# hbridge.net
KiCad netlist of a schematic drawn in EAGLE
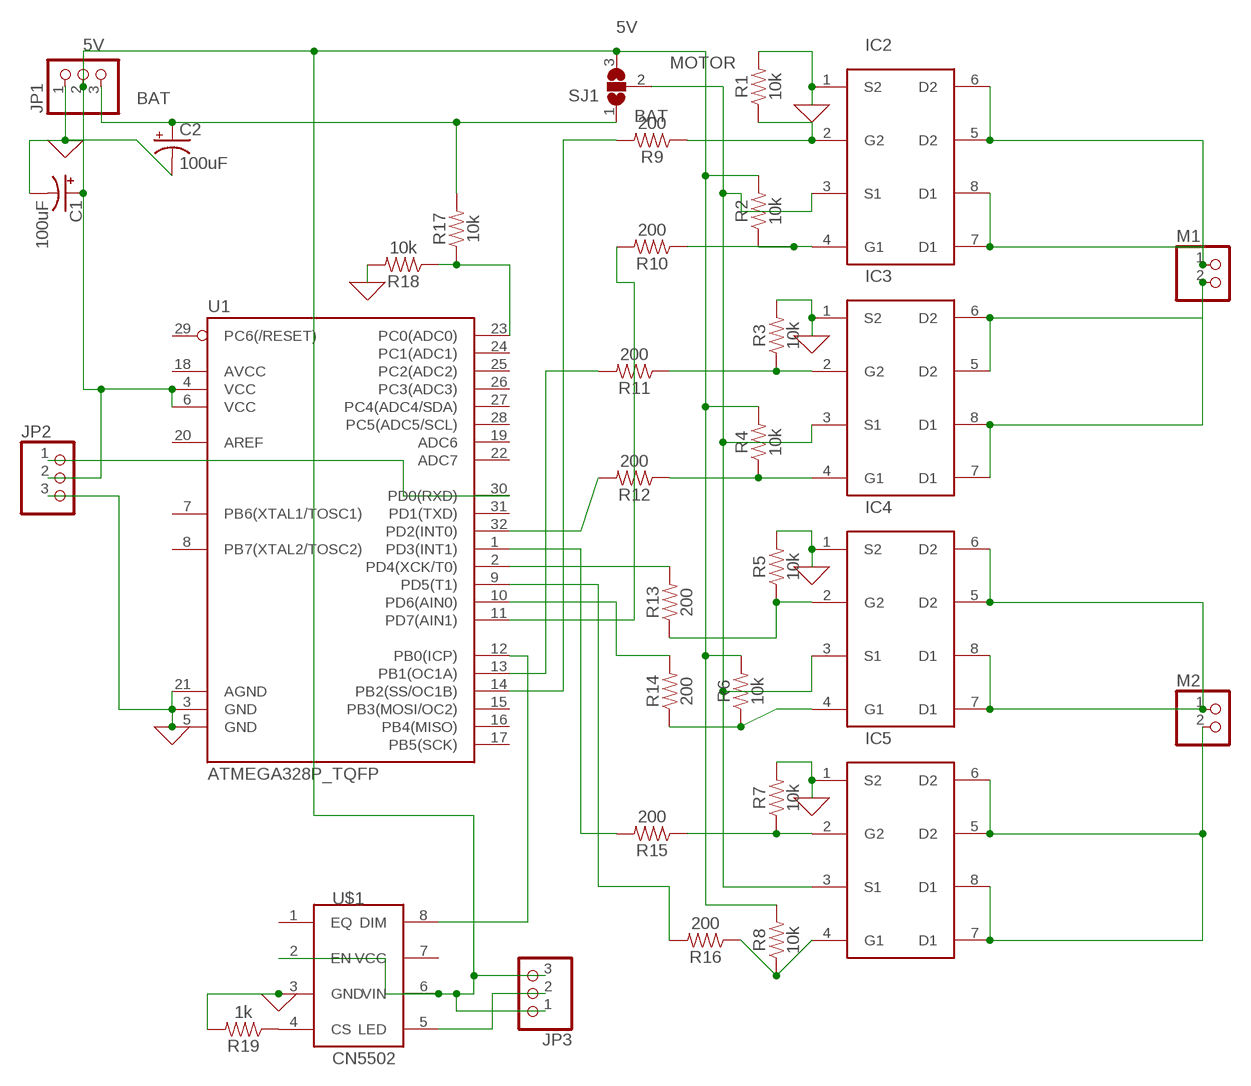
[diagram p0: schematic, sheet 1]

(export (version "E")
  (design (tool "Eeschema 10.0.6"))
  (components
    (comp (ref "C1")
      (value "100uF")
      (footprint "eagle-import:CPOL-RADIAL-2.5MM-6.5MM")
      (libsource (lib "eagle-import") (part "100UF-POLAR-RADIAL-2.5MM-25V-20%"))
    )
    (comp (ref "C2")
      (value "100uF")
      (footprint "eagle-import:CPOL-RADIAL-2.5MM-6.5MM")
      (libsource (lib "eagle-import") (part "100UF-POLAR-RADIAL-2.5MM-25V-20%"))
    )
    (comp (ref "IC2")
      (value "AO4606SOIC8")
      (footprint "eagle-import:SOIC8")
      (libsource (lib "eagle-import") (part "AO4606SOIC8"))
    )
    (comp (ref "IC3")
      (value "AO4606SOIC8")
      (footprint "eagle-import:SOIC8")
      (libsource (lib "eagle-import") (part "AO4606SOIC8"))
    )
    (comp (ref "IC4")
      (value "AO4606SOIC8")
      (footprint "eagle-import:SOIC8")
      (libsource (lib "eagle-import") (part "AO4606SOIC8"))
    )
    (comp (ref "IC5")
      (value "AO4606SOIC8")
      (footprint "eagle-import:SOIC8")
      (libsource (lib "eagle-import") (part "AO4606SOIC8"))
    )
    (comp (ref "JP1")
      (value "PINHD-1X3")
      (footprint "eagle-import:1X03")
      (libsource (lib "eagle-import") (part "PINHD-1X3"))
    )
    (comp (ref "JP2")
      (value "PINHD-1X3")
      (footprint "eagle-import:1X03")
      (libsource (lib "eagle-import") (part "PINHD-1X3"))
    )
    (comp (ref "JP3")
      (value "PINHD-1X3")
      (footprint "eagle-import:1X03")
      (libsource (lib "eagle-import") (part "PINHD-1X3"))
    )
    (comp (ref "M1")
      (value "PINHD-1X2")
      (footprint "eagle-import:1X02")
      (libsource (lib "eagle-import") (part "PINHD-1X2"))
    )
    (comp (ref "M2")
      (value "PINHD-1X2")
      (footprint "eagle-import:1X02")
      (libsource (lib "eagle-import") (part "PINHD-1X2"))
    )
    (comp (ref "R1")
      (value "10k")
      (footprint "eagle-import:0603")
      (libsource (lib "eagle-import") (part "10KOHM-0603-1/10W-1%"))
    )
    (comp (ref "R2")
      (value "10k")
      (footprint "eagle-import:0603")
      (libsource (lib "eagle-import") (part "10KOHM-0603-1/10W-1%"))
    )
    (comp (ref "R3")
      (value "10k")
      (footprint "eagle-import:0603")
      (libsource (lib "eagle-import") (part "10KOHM-0603-1/10W-1%"))
    )
    (comp (ref "R4")
      (value "10k")
      (footprint "eagle-import:0603")
      (libsource (lib "eagle-import") (part "10KOHM-0603-1/10W-1%"))
    )
    (comp (ref "R5")
      (value "10k")
      (footprint "eagle-import:0603")
      (libsource (lib "eagle-import") (part "10KOHM-0603-1/10W-1%"))
    )
    (comp (ref "R6")
      (value "10k")
      (footprint "eagle-import:0603")
      (libsource (lib "eagle-import") (part "10KOHM-0603-1/10W-1%"))
    )
    (comp (ref "R7")
      (value "10k")
      (footprint "eagle-import:0603")
      (libsource (lib "eagle-import") (part "10KOHM-0603-1/10W-1%"))
    )
    (comp (ref "R8")
      (value "10k")
      (footprint "eagle-import:0603")
      (libsource (lib "eagle-import") (part "10KOHM-0603-1/10W-1%"))
    )
    (comp (ref "R9")
      (value "200")
      (footprint "eagle-import:0603")
      (libsource (lib "eagle-import") (part "200OHM-0603-1/10W-1%"))
    )
    (comp (ref "R10")
      (value "200")
      (footprint "eagle-import:0603")
      (libsource (lib "eagle-import") (part "200OHM-0603-1/10W-1%"))
    )
    (comp (ref "R11")
      (value "200")
      (footprint "eagle-import:0603")
      (libsource (lib "eagle-import") (part "200OHM-0603-1/10W-1%"))
    )
    (comp (ref "R12")
      (value "200")
      (footprint "eagle-import:0603")
      (libsource (lib "eagle-import") (part "200OHM-0603-1/10W-1%"))
    )
    (comp (ref "R13")
      (value "200")
      (footprint "eagle-import:0603")
      (libsource (lib "eagle-import") (part "200OHM-0603-1/10W-1%"))
    )
    (comp (ref "R14")
      (value "200")
      (footprint "eagle-import:0603")
      (libsource (lib "eagle-import") (part "200OHM-0603-1/10W-1%"))
    )
    (comp (ref "R15")
      (value "200")
      (footprint "eagle-import:0603")
      (libsource (lib "eagle-import") (part "200OHM-0603-1/10W-1%"))
    )
    (comp (ref "R16")
      (value "200")
      (footprint "eagle-import:0603")
      (libsource (lib "eagle-import") (part "200OHM-0603-1/10W-1%"))
    )
    (comp (ref "R17")
      (value "10k")
      (footprint "eagle-import:AXIAL-0.3")
      (libsource (lib "eagle-import") (part "10KOHM-HORIZ-1/4W-1%"))
    )
    (comp (ref "R18")
      (value "10k")
      (footprint "eagle-import:AXIAL-0.3")
      (libsource (lib "eagle-import") (part "10KOHM-HORIZ-1/4W-1%"))
    )
    (comp (ref "R19")
      (value "1k")
      (footprint "eagle-import:AXIAL-0.3")
      (libsource (lib "eagle-import") (part "1KOHM-HORIZ-1/4W-1%"))
    )
    (comp (ref "SJ1")
      (value "SJ2W")
      (footprint "eagle-import:SJ_2")
      (libsource (lib "eagle-import") (part "SJ2W"))
    )
    (comp (ref "U$1")
      (value "CN5502")
      (footprint "eagle-import:SOIC8")
      (libsource (lib "eagle-import") (part "CN5502"))
    )
    (comp (ref "U1")
      (value "ATMEGA328P_TQFP")
      (footprint "eagle-import:TQFP32-08")
      (libsource (lib "eagle-import") (part "ATMEGA328P_TQFP"))
    )
  )
  (nets
    (net (code "1") (name "/5V") (class "Default")
      (node (ref "C1") (pin "1") (pinfunction "+_1") (pintype "passive"))
      (node (ref "JP1") (pin "2") (pinfunction "2_2") (pintype "passive"))
      (node (ref "JP2") (pin "2") (pinfunction "2_2") (pintype "passive"))
      (node (ref "JP3") (pin "1") (pinfunction "1_1") (pintype "passive"))
      (node (ref "JP3") (pin "3") (pinfunction "3_3") (pintype "passive"))
      (node (ref "R2") (pin "2") (pinfunction "2_2") (pintype "passive"))
      (node (ref "R4") (pin "2") (pinfunction "2_2") (pintype "passive"))
      (node (ref "R6") (pin "2") (pinfunction "2_2") (pintype "passive"))
      (node (ref "R8") (pin "2") (pinfunction "2_2") (pintype "passive"))
      (node (ref "SJ1") (pin "3") (pinfunction "3_3") (pintype "passive"))
      (node (ref "U$1") (pin "2") (pinfunction "EN_2") (pintype "input"))
      (node (ref "U$1") (pin "6") (pinfunction "VIN_6") (pintype "power_in"))
      (node (ref "U1") (pin "4") (pinfunction "VCC_4") (pintype "bidirectional"))
      (node (ref "U1") (pin "6") (pinfunction "VCC_6") (pintype "bidirectional"))
    )
    (net (code "2") (name "/BAT") (class "Default")
      (node (ref "C2") (pin "1") (pinfunction "+_1") (pintype "passive"))
      (node (ref "JP1") (pin "3") (pinfunction "3_3") (pintype "passive"))
      (node (ref "R17") (pin "P$2") (pinfunction "2_P$2") (pintype "passive"))
      (node (ref "SJ1") (pin "1") (pinfunction "1_1") (pintype "passive"))
    )
    (net (code "3") (name "/MOTOR") (class "Default")
      (node (ref "IC2") (pin "3") (pinfunction "S1_3") (pintype "bidirectional"))
      (node (ref "IC3") (pin "3") (pinfunction "S1_3") (pintype "bidirectional"))
      (node (ref "IC4") (pin "3") (pinfunction "S1_3") (pintype "bidirectional"))
      (node (ref "IC5") (pin "3") (pinfunction "S1_3") (pintype "bidirectional"))
      (node (ref "SJ1") (pin "2") (pinfunction "2_2") (pintype "passive"))
    )
    (net (code "4") (name "/VCC") (class "Default")
      (node (ref "U$1") (pin "7") (pinfunction "VCC_7") (pintype "power_in"))
    )
    (net (code "5") (name "GND") (class "Default")
      (node (ref "C1") (pin "2") (pinfunction "-_2") (pintype "passive"))
      (node (ref "C2") (pin "2") (pinfunction "-_2") (pintype "passive"))
      (node (ref "IC2") (pin "1") (pinfunction "S2_1") (pintype "bidirectional"))
      (node (ref "IC3") (pin "1") (pinfunction "S2_1") (pintype "bidirectional"))
      (node (ref "IC4") (pin "1") (pinfunction "S2_1") (pintype "bidirectional"))
      (node (ref "IC5") (pin "1") (pinfunction "S2_1") (pintype "bidirectional"))
      (node (ref "JP1") (pin "1") (pinfunction "1_1") (pintype "passive"))
      (node (ref "JP2") (pin "3") (pinfunction "3_3") (pintype "passive"))
      (node (ref "R1") (pin "2") (pinfunction "2_2") (pintype "passive"))
      (node (ref "R18") (pin "P$2") (pinfunction "2_P$2") (pintype "passive"))
      (node (ref "R19") (pin "P$2") (pinfunction "2_P$2") (pintype "passive"))
      (node (ref "R3") (pin "2") (pinfunction "2_2") (pintype "passive"))
      (node (ref "R5") (pin "2") (pinfunction "2_2") (pintype "passive"))
      (node (ref "R7") (pin "2") (pinfunction "2_2") (pintype "passive"))
      (node (ref "U$1") (pin "3") (pinfunction "GND_3") (pintype "power_in"))
      (node (ref "U1") (pin "21") (pinfunction "AGND_21") (pintype "bidirectional"))
      (node (ref "U1") (pin "3") (pinfunction "GND_3") (pintype "bidirectional"))
      (node (ref "U1") (pin "5") (pinfunction "GND_5") (pintype "bidirectional"))
    )
    (net (code "6") (name "Net-(IC2-D1-Pad7)") (class "Default")
      (node (ref "IC2") (pin "5") (pinfunction "D2_5") (pintype "bidirectional"))
      (node (ref "IC2") (pin "6") (pinfunction "D2_6") (pintype "bidirectional"))
      (node (ref "IC2") (pin "7") (pinfunction "D1_7") (pintype "bidirectional"))
      (node (ref "IC2") (pin "8") (pinfunction "D1_8") (pintype "bidirectional"))
      (node (ref "M1") (pin "1") (pinfunction "1_1") (pintype "passive"))
    )
    (net (code "7") (name "Net-(IC2-G1)") (class "Default")
      (node (ref "IC2") (pin "4") (pinfunction "G1_4") (pintype "bidirectional"))
      (node (ref "R10") (pin "1") (pinfunction "1_1") (pintype "passive"))
      (node (ref "R2") (pin "1") (pinfunction "1_1") (pintype "passive"))
    )
    (net (code "8") (name "Net-(IC2-G2)") (class "Default")
      (node (ref "IC2") (pin "2") (pinfunction "G2_2") (pintype "bidirectional"))
      (node (ref "R1") (pin "1") (pinfunction "1_1") (pintype "passive"))
      (node (ref "R9") (pin "1") (pinfunction "1_1") (pintype "passive"))
    )
    (net (code "9") (name "Net-(IC3-D1-Pad7)") (class "Default")
      (node (ref "IC3") (pin "5") (pinfunction "D2_5") (pintype "bidirectional"))
      (node (ref "IC3") (pin "6") (pinfunction "D2_6") (pintype "bidirectional"))
      (node (ref "IC3") (pin "7") (pinfunction "D1_7") (pintype "bidirectional"))
      (node (ref "IC3") (pin "8") (pinfunction "D1_8") (pintype "bidirectional"))
      (node (ref "M1") (pin "2") (pinfunction "2_2") (pintype "passive"))
    )
    (net (code "10") (name "Net-(IC3-G1)") (class "Default")
      (node (ref "IC3") (pin "4") (pinfunction "G1_4") (pintype "bidirectional"))
      (node (ref "R12") (pin "1") (pinfunction "1_1") (pintype "passive"))
      (node (ref "R4") (pin "1") (pinfunction "1_1") (pintype "passive"))
    )
    (net (code "11") (name "Net-(IC3-G2)") (class "Default")
      (node (ref "IC3") (pin "2") (pinfunction "G2_2") (pintype "bidirectional"))
      (node (ref "R11") (pin "1") (pinfunction "1_1") (pintype "passive"))
      (node (ref "R3") (pin "1") (pinfunction "1_1") (pintype "passive"))
    )
    (net (code "12") (name "Net-(IC4-D1-Pad7)") (class "Default")
      (node (ref "IC4") (pin "5") (pinfunction "D2_5") (pintype "bidirectional"))
      (node (ref "IC4") (pin "6") (pinfunction "D2_6") (pintype "bidirectional"))
      (node (ref "IC4") (pin "7") (pinfunction "D1_7") (pintype "bidirectional"))
      (node (ref "IC4") (pin "8") (pinfunction "D1_8") (pintype "bidirectional"))
      (node (ref "M2") (pin "1") (pinfunction "1_1") (pintype "passive"))
    )
    (net (code "13") (name "Net-(IC4-G1)") (class "Default")
      (node (ref "IC4") (pin "4") (pinfunction "G1_4") (pintype "bidirectional"))
      (node (ref "R14") (pin "1") (pinfunction "1_1") (pintype "passive"))
      (node (ref "R6") (pin "1") (pinfunction "1_1") (pintype "passive"))
    )
    (net (code "14") (name "Net-(IC4-G2)") (class "Default")
      (node (ref "IC4") (pin "2") (pinfunction "G2_2") (pintype "bidirectional"))
      (node (ref "R13") (pin "1") (pinfunction "1_1") (pintype "passive"))
      (node (ref "R5") (pin "1") (pinfunction "1_1") (pintype "passive"))
    )
    (net (code "15") (name "Net-(IC5-D1-Pad7)") (class "Default")
      (node (ref "IC5") (pin "5") (pinfunction "D2_5") (pintype "bidirectional"))
      (node (ref "IC5") (pin "6") (pinfunction "D2_6") (pintype "bidirectional"))
      (node (ref "IC5") (pin "7") (pinfunction "D1_7") (pintype "bidirectional"))
      (node (ref "IC5") (pin "8") (pinfunction "D1_8") (pintype "bidirectional"))
      (node (ref "M2") (pin "2") (pinfunction "2_2") (pintype "passive"))
    )
    (net (code "16") (name "Net-(IC5-G1)") (class "Default")
      (node (ref "IC5") (pin "4") (pinfunction "G1_4") (pintype "bidirectional"))
      (node (ref "R16") (pin "1") (pinfunction "1_1") (pintype "passive"))
      (node (ref "R8") (pin "1") (pinfunction "1_1") (pintype "passive"))
    )
    (net (code "17") (name "Net-(IC5-G2)") (class "Default")
      (node (ref "IC5") (pin "2") (pinfunction "G2_2") (pintype "bidirectional"))
      (node (ref "R15") (pin "1") (pinfunction "1_1") (pintype "passive"))
      (node (ref "R7") (pin "1") (pinfunction "1_1") (pintype "passive"))
    )
    (net (code "18") (name "Net-(R17-1)") (class "Default")
      (node (ref "R17") (pin "P$1") (pinfunction "1_P$1") (pintype "passive"))
      (node (ref "R18") (pin "P$1") (pinfunction "1_P$1") (pintype "passive"))
      (node (ref "U1") (pin "23") (pinfunction "PC0(ADC0)_23") (pintype "bidirectional"))
    )
    (net (code "19") (name "Net-(R19-1)") (class "Default")
      (node (ref "R19") (pin "P$1") (pinfunction "1_P$1") (pintype "passive"))
      (node (ref "U$1") (pin "4") (pinfunction "CS_4") (pintype "output"))
    )
    (net (code "20") (name "Net-(U$1-DIM)") (class "Default")
      (node (ref "U$1") (pin "8") (pinfunction "DIM_8") (pintype "input"))
      (node (ref "U1") (pin "12") (pinfunction "PB0(ICP)_12") (pintype "bidirectional"))
    )
    (net (code "21") (name "Net-(U$1-LED)") (class "Default")
      (node (ref "JP3") (pin "2") (pinfunction "2_2") (pintype "passive"))
      (node (ref "U$1") (pin "5") (pinfunction "LED_5") (pintype "output"))
    )
    (net (code "22") (name "Net-(U1-PB1(OC1A))") (class "Default")
      (node (ref "R11") (pin "2") (pinfunction "2_2") (pintype "passive"))
      (node (ref "U1") (pin "13") (pinfunction "PB1(OC1A)_13") (pintype "bidirectional"))
    )
    (net (code "23") (name "Net-(U1-PB2(SS{slash}OC1B))") (class "Default")
      (node (ref "R9") (pin "2") (pinfunction "2_2") (pintype "passive"))
      (node (ref "U1") (pin "14") (pinfunction "PB2(SS/OC1B)_14") (pintype "bidirectional"))
    )
    (net (code "24") (name "Net-(U1-PD0(RXD))") (class "Default")
      (node (ref "JP2") (pin "1") (pinfunction "1_1") (pintype "passive"))
      (node (ref "U1") (pin "30") (pinfunction "PD0(RXD)_30") (pintype "bidirectional"))
    )
    (net (code "25") (name "Net-(U1-PD2(INT0))") (class "Default")
      (node (ref "R12") (pin "2") (pinfunction "2_2") (pintype "passive"))
      (node (ref "U1") (pin "32") (pinfunction "PD2(INT0)_32") (pintype "bidirectional"))
    )
    (net (code "26") (name "Net-(U1-PD3(INT1))") (class "Default")
      (node (ref "R15") (pin "2") (pinfunction "2_2") (pintype "passive"))
      (node (ref "U1") (pin "1") (pinfunction "PD3(INT1)_1") (pintype "bidirectional"))
    )
    (net (code "27") (name "Net-(U1-PD4(XCK{slash}T0))") (class "Default")
      (node (ref "R13") (pin "2") (pinfunction "2_2") (pintype "passive"))
      (node (ref "U1") (pin "2") (pinfunction "PD4(XCK/T0)_2") (pintype "bidirectional"))
    )
    (net (code "28") (name "Net-(U1-PD5(T1))") (class "Default")
      (node (ref "R16") (pin "2") (pinfunction "2_2") (pintype "passive"))
      (node (ref "U1") (pin "9") (pinfunction "PD5(T1)_9") (pintype "bidirectional"))
    )
    (net (code "29") (name "Net-(U1-PD6(AIN0))") (class "Default")
      (node (ref "R14") (pin "2") (pinfunction "2_2") (pintype "passive"))
      (node (ref "U1") (pin "10") (pinfunction "PD6(AIN0)_10") (pintype "bidirectional"))
    )
    (net (code "30") (name "Net-(U1-PD7(AIN1))") (class "Default")
      (node (ref "R10") (pin "2") (pinfunction "2_2") (pintype "passive"))
      (node (ref "U1") (pin "11") (pinfunction "PD7(AIN1)_11") (pintype "bidirectional"))
    )
    (net (code "31") (name "unconnected-(U$1-EQ-Pad1)") (class "Default")
      (node (ref "U$1") (pin "1") (pinfunction "EQ_1") (pintype "output"))
    )
    (net (code "32") (name "unconnected-(U1-ADC6-Pad19)") (class "Default")
      (node (ref "U1") (pin "19") (pinfunction "ADC6_19") (pintype "bidirectional"))
    )
    (net (code "33") (name "unconnected-(U1-ADC7-Pad22)") (class "Default")
      (node (ref "U1") (pin "22") (pinfunction "ADC7_22") (pintype "bidirectional"))
    )
    (net (code "34") (name "unconnected-(U1-AREF-Pad20)") (class "Default")
      (node (ref "U1") (pin "20") (pinfunction "AREF_20") (pintype "bidirectional"))
    )
    (net (code "35") (name "unconnected-(U1-AVCC-Pad18)") (class "Default")
      (node (ref "U1") (pin "18") (pinfunction "AVCC_18") (pintype "bidirectional"))
    )
    (net (code "36") (name "unconnected-(U1-PB3(MOSI{slash}OC2)-Pad15)") (class "Default")
      (node (ref "U1") (pin "15") (pinfunction "PB3(MOSI/OC2)_15") (pintype "bidirectional"))
    )
    (net (code "37") (name "unconnected-(U1-PB4(MISO)-Pad16)") (class "Default")
      (node (ref "U1") (pin "16") (pinfunction "PB4(MISO)_16") (pintype "bidirectional"))
    )
    (net (code "38") (name "unconnected-(U1-PB5(SCK)-Pad17)") (class "Default")
      (node (ref "U1") (pin "17") (pinfunction "PB5(SCK)_17") (pintype "bidirectional"))
    )
    (net (code "39") (name "unconnected-(U1-PB6(XTAL1{slash}TOSC1)-Pad7)") (class "Default")
      (node (ref "U1") (pin "7") (pinfunction "PB6(XTAL1/TOSC1)_7") (pintype "bidirectional"))
    )
    (net (code "40") (name "unconnected-(U1-PB7(XTAL2{slash}TOSC2)-Pad8)") (class "Default")
      (node (ref "U1") (pin "8") (pinfunction "PB7(XTAL2/TOSC2)_8") (pintype "bidirectional"))
    )
    (net (code "41") (name "unconnected-(U1-PC1(ADC1)-Pad24)") (class "Default")
      (node (ref "U1") (pin "24") (pinfunction "PC1(ADC1)_24") (pintype "bidirectional"))
    )
    (net (code "42") (name "unconnected-(U1-PC2(ADC2)-Pad25)") (class "Default")
      (node (ref "U1") (pin "25") (pinfunction "PC2(ADC2)_25") (pintype "bidirectional"))
    )
    (net (code "43") (name "unconnected-(U1-PC3(ADC3)-Pad26)") (class "Default")
      (node (ref "U1") (pin "26") (pinfunction "PC3(ADC3)_26") (pintype "bidirectional"))
    )
    (net (code "44") (name "unconnected-(U1-PC4(ADC4{slash}SDA)-Pad27)") (class "Default")
      (node (ref "U1") (pin "27") (pinfunction "PC4(ADC4/SDA)_27") (pintype "bidirectional"))
    )
    (net (code "45") (name "unconnected-(U1-PC5(ADC5{slash}SCL)-Pad28)") (class "Default")
      (node (ref "U1") (pin "28") (pinfunction "PC5(ADC5/SCL)_28") (pintype "bidirectional"))
    )
    (net (code "46") (name "unconnected-(U1-PC6({slash}RESET)-Pad29)") (class "Default")
      (node (ref "U1") (pin "29") (pinfunction "PC6(/RESET)_29") (pintype "bidirectional"))
    )
    (net (code "47") (name "unconnected-(U1-PD1(TXD)-Pad31)") (class "Default")
      (node (ref "U1") (pin "31") (pinfunction "PD1(TXD)_31") (pintype "bidirectional"))
    )
  )
)
